# AD9434-500.net
KiCad netlist of a schematic drawn in Altium Designer
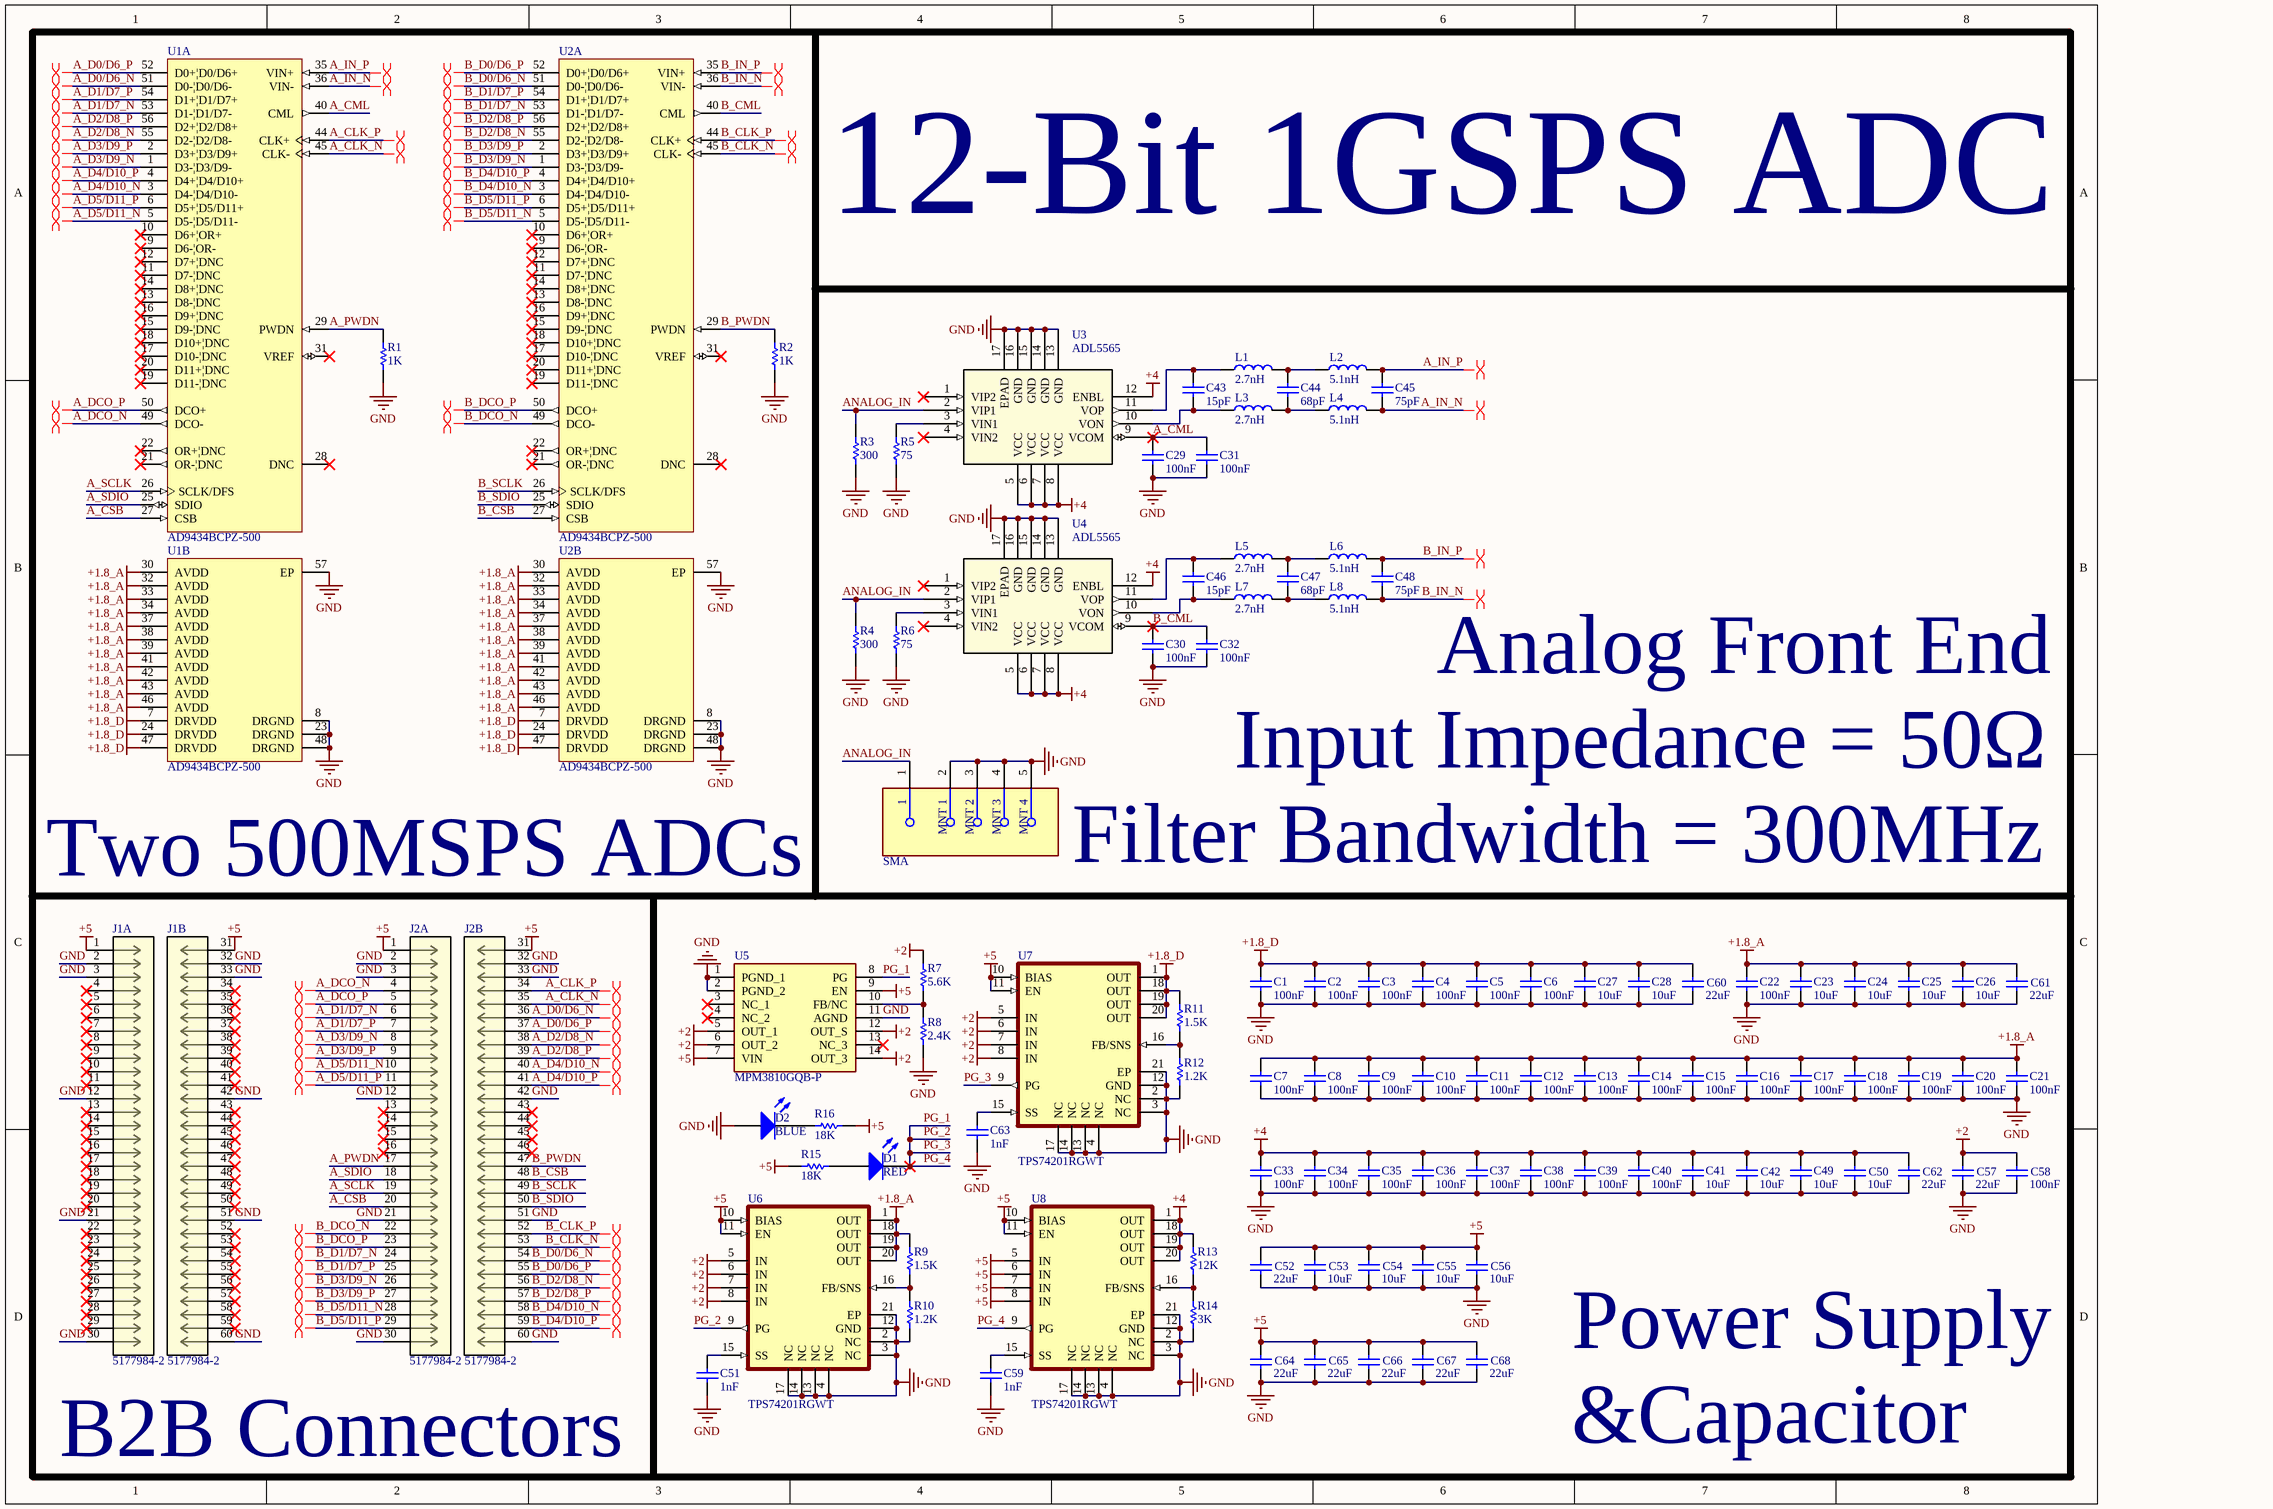
[diagram p0: AD9434-500.SchDoc]

(export (version "E")
  (design (tool "Eeschema 10.0.6"))
  (components
    (comp (ref "C1")
      (value "100nF")
      (footprint "0402")
      (description "Capacitor")
      (fields (field (name "PUBLISHER") "Altium Limited"))
      (libsource (lib "My Footprint") (part "CAP"))
    )
    (comp (ref "C2")
      (value "100nF")
      (footprint "0402")
      (description "Capacitor")
      (fields (field (name "PUBLISHER") "Altium Limited"))
      (libsource (lib "My Footprint") (part "CAP"))
    )
    (comp (ref "C3")
      (value "100nF")
      (footprint "0402")
      (description "Capacitor")
      (fields (field (name "PUBLISHER") "Altium Limited"))
      (libsource (lib "My Footprint") (part "CAP"))
    )
    (comp (ref "C4")
      (value "100nF")
      (footprint "0402")
      (description "Capacitor")
      (fields (field (name "PUBLISHER") "Altium Limited"))
      (libsource (lib "My Footprint") (part "CAP"))
    )
    (comp (ref "C5")
      (value "100nF")
      (footprint "0402")
      (description "Capacitor")
      (fields (field (name "PUBLISHER") "Altium Limited"))
      (libsource (lib "My Footprint") (part "CAP"))
    )
    (comp (ref "C6")
      (value "100nF")
      (footprint "0402")
      (description "Capacitor")
      (fields (field (name "PUBLISHER") "Altium Limited"))
      (libsource (lib "My Footprint") (part "CAP"))
    )
    (comp (ref "C7")
      (value "100nF")
      (footprint "0402")
      (description "Capacitor")
      (fields (field (name "PUBLISHER") "Altium Limited"))
      (libsource (lib "My Footprint") (part "CAP"))
    )
    (comp (ref "C8")
      (value "100nF")
      (footprint "0402")
      (description "Capacitor")
      (fields (field (name "PUBLISHER") "Altium Limited"))
      (libsource (lib "My Footprint") (part "CAP"))
    )
    (comp (ref "C9")
      (value "100nF")
      (footprint "0402")
      (description "Capacitor")
      (fields (field (name "PUBLISHER") "Altium Limited"))
      (libsource (lib "My Footprint") (part "CAP"))
    )
    (comp (ref "C10")
      (value "100nF")
      (footprint "0402")
      (description "Capacitor")
      (fields (field (name "PUBLISHER") "Altium Limited"))
      (libsource (lib "My Footprint") (part "CAP"))
    )
    (comp (ref "C11")
      (value "100nF")
      (footprint "0402")
      (description "Capacitor")
      (fields (field (name "PUBLISHER") "Altium Limited"))
      (libsource (lib "My Footprint") (part "CAP"))
    )
    (comp (ref "C12")
      (value "100nF")
      (footprint "0402")
      (description "Capacitor")
      (fields (field (name "PUBLISHER") "Altium Limited"))
      (libsource (lib "My Footprint") (part "CAP"))
    )
    (comp (ref "C13")
      (value "100nF")
      (footprint "0402")
      (description "Capacitor")
      (fields (field (name "PUBLISHER") "Altium Limited"))
      (libsource (lib "My Footprint") (part "CAP"))
    )
    (comp (ref "C14")
      (value "100nF")
      (footprint "0402")
      (description "Capacitor")
      (fields (field (name "PUBLISHER") "Altium Limited"))
      (libsource (lib "My Footprint") (part "CAP"))
    )
    (comp (ref "C15")
      (value "100nF")
      (footprint "0402")
      (description "Capacitor")
      (fields (field (name "PUBLISHER") "Altium Limited"))
      (libsource (lib "My Footprint") (part "CAP"))
    )
    (comp (ref "C16")
      (value "100nF")
      (footprint "0402")
      (description "Capacitor")
      (fields (field (name "PUBLISHER") "Altium Limited"))
      (libsource (lib "My Footprint") (part "CAP"))
    )
    (comp (ref "C17")
      (value "100nF")
      (footprint "0402")
      (description "Capacitor")
      (fields (field (name "PUBLISHER") "Altium Limited"))
      (libsource (lib "My Footprint") (part "CAP"))
    )
    (comp (ref "C18")
      (value "100nF")
      (footprint "0402")
      (description "Capacitor")
      (fields (field (name "PUBLISHER") "Altium Limited"))
      (libsource (lib "My Footprint") (part "CAP"))
    )
    (comp (ref "C19")
      (value "100nF")
      (footprint "0402")
      (description "Capacitor")
      (fields (field (name "PUBLISHER") "Altium Limited"))
      (libsource (lib "My Footprint") (part "CAP"))
    )
    (comp (ref "C20")
      (value "100nF")
      (footprint "0402")
      (description "Capacitor")
      (fields (field (name "PUBLISHER") "Altium Limited"))
      (libsource (lib "My Footprint") (part "CAP"))
    )
    (comp (ref "C21")
      (value "100nF")
      (footprint "0402")
      (description "Capacitor")
      (fields (field (name "PUBLISHER") "Altium Limited"))
      (libsource (lib "My Footprint") (part "CAP"))
    )
    (comp (ref "C22")
      (value "100nF")
      (footprint "0402")
      (description "Capacitor")
      (fields (field (name "PUBLISHER") "Altium Limited"))
      (libsource (lib "My Footprint") (part "CAP"))
    )
    (comp (ref "C23")
      (value "10uF")
      (footprint "0402")
      (description "Capacitor")
      (fields (field (name "PUBLISHER") "Altium Limited"))
      (libsource (lib "My Footprint") (part "CAP"))
    )
    (comp (ref "C24")
      (value "10uF")
      (footprint "0402")
      (description "Capacitor")
      (fields (field (name "PUBLISHER") "Altium Limited"))
      (libsource (lib "My Footprint") (part "CAP"))
    )
    (comp (ref "C25")
      (value "10uF")
      (footprint "0402")
      (description "Capacitor")
      (fields (field (name "PUBLISHER") "Altium Limited"))
      (libsource (lib "My Footprint") (part "CAP"))
    )
    (comp (ref "C26")
      (value "10uF")
      (footprint "0402")
      (description "Capacitor")
      (fields (field (name "PUBLISHER") "Altium Limited"))
      (libsource (lib "My Footprint") (part "CAP"))
    )
    (comp (ref "C27")
      (value "10uF")
      (footprint "0402")
      (description "Capacitor")
      (fields (field (name "PUBLISHER") "Altium Limited"))
      (libsource (lib "My Footprint") (part "CAP"))
    )
    (comp (ref "C28")
      (value "10uF")
      (footprint "0402")
      (description "Capacitor")
      (fields (field (name "PUBLISHER") "Altium Limited"))
      (libsource (lib "My Footprint") (part "CAP"))
    )
    (comp (ref "C29")
      (value "100nF")
      (footprint "0402")
      (description "Capacitor")
      (fields (field (name "PUBLISHER") "Altium Limited"))
      (libsource (lib "My Footprint") (part "CAP"))
    )
    (comp (ref "C30")
      (value "100nF")
      (footprint "0402")
      (description "Capacitor")
      (fields (field (name "PUBLISHER") "Altium Limited"))
      (libsource (lib "My Footprint") (part "CAP"))
    )
    (comp (ref "C31")
      (value "100nF")
      (footprint "0402")
      (description "Capacitor")
      (fields (field (name "PUBLISHER") "Altium Limited"))
      (libsource (lib "My Footprint") (part "CAP"))
    )
    (comp (ref "C32")
      (value "100nF")
      (footprint "0402")
      (description "Capacitor")
      (fields (field (name "PUBLISHER") "Altium Limited"))
      (libsource (lib "My Footprint") (part "CAP"))
    )
    (comp (ref "C33")
      (value "100nF")
      (footprint "0402")
      (description "Capacitor")
      (fields (field (name "PUBLISHER") "Altium Limited"))
      (libsource (lib "My Footprint") (part "CAP"))
    )
    (comp (ref "C34")
      (value "100nF")
      (footprint "0402")
      (description "Capacitor")
      (fields (field (name "PUBLISHER") "Altium Limited"))
      (libsource (lib "My Footprint") (part "CAP"))
    )
    (comp (ref "C35")
      (value "100nF")
      (footprint "0402")
      (description "Capacitor")
      (fields (field (name "PUBLISHER") "Altium Limited"))
      (libsource (lib "My Footprint") (part "CAP"))
    )
    (comp (ref "C36")
      (value "100nF")
      (footprint "0402")
      (description "Capacitor")
      (fields (field (name "PUBLISHER") "Altium Limited"))
      (libsource (lib "My Footprint") (part "CAP"))
    )
    (comp (ref "C37")
      (value "100nF")
      (footprint "0402")
      (description "Capacitor")
      (fields (field (name "PUBLISHER") "Altium Limited"))
      (libsource (lib "My Footprint") (part "CAP"))
    )
    (comp (ref "C38")
      (value "100nF")
      (footprint "0402")
      (description "Capacitor")
      (fields (field (name "PUBLISHER") "Altium Limited"))
      (libsource (lib "My Footprint") (part "CAP"))
    )
    (comp (ref "C39")
      (value "100nF")
      (footprint "0402")
      (description "Capacitor")
      (fields (field (name "PUBLISHER") "Altium Limited"))
      (libsource (lib "My Footprint") (part "CAP"))
    )
    (comp (ref "C40")
      (value "100nF")
      (footprint "0402")
      (description "Capacitor")
      (fields (field (name "PUBLISHER") "Altium Limited"))
      (libsource (lib "My Footprint") (part "CAP"))
    )
    (comp (ref "C41")
      (value "10uF")
      (footprint "0402")
      (description "Capacitor")
      (fields (field (name "PUBLISHER") "Altium Limited"))
      (libsource (lib "My Footprint") (part "CAP"))
    )
    (comp (ref "C42")
      (value "10uF")
      (footprint "0402")
      (description "Capacitor")
      (fields (field (name "PUBLISHER") "Altium Limited"))
      (libsource (lib "My Footprint") (part "CAP"))
    )
    (comp (ref "C43")
      (value "15pF")
      (footprint "0402")
      (description "Capacitor")
      (fields (field (name "PUBLISHER") "Altium Limited"))
      (libsource (lib "My Footprint") (part "CAP"))
    )
    (comp (ref "C44")
      (value "68pF")
      (footprint "0402")
      (description "Capacitor")
      (fields (field (name "PUBLISHER") "Altium Limited"))
      (libsource (lib "My Footprint") (part "CAP"))
    )
    (comp (ref "C45")
      (value "75pF")
      (footprint "0402")
      (description "Capacitor")
      (fields (field (name "PUBLISHER") "Altium Limited"))
      (libsource (lib "My Footprint") (part "CAP"))
    )
    (comp (ref "C46")
      (value "15pF")
      (footprint "0402")
      (description "Capacitor")
      (fields (field (name "PUBLISHER") "Altium Limited"))
      (libsource (lib "My Footprint") (part "CAP"))
    )
    (comp (ref "C47")
      (value "68pF")
      (footprint "0402")
      (description "Capacitor")
      (fields (field (name "PUBLISHER") "Altium Limited"))
      (libsource (lib "My Footprint") (part "CAP"))
    )
    (comp (ref "C48")
      (value "75pF")
      (footprint "0402")
      (description "Capacitor")
      (fields (field (name "PUBLISHER") "Altium Limited"))
      (libsource (lib "My Footprint") (part "CAP"))
    )
    (comp (ref "C49")
      (value "10uF")
      (footprint "0402")
      (description "Capacitor")
      (fields (field (name "PUBLISHER") "Altium Limited"))
      (libsource (lib "My Footprint") (part "CAP"))
    )
    (comp (ref "C50")
      (value "10uF")
      (footprint "0402")
      (description "Capacitor")
      (fields (field (name "PUBLISHER") "Altium Limited"))
      (libsource (lib "My Footprint") (part "CAP"))
    )
    (comp (ref "C51")
      (value "1nF")
      (footprint "0402")
      (description "Capacitor")
      (fields (field (name "PUBLISHER") "Altium Limited"))
      (libsource (lib "My Footprint") (part "CAP"))
    )
    (comp (ref "C52")
      (value "22uF")
      (footprint "6-0805_L")
      (description "Capacitor")
      (fields (field (name "PUBLISHER") "Altium Limited"))
      (libsource (lib "My Footprint") (part "CAP"))
    )
    (comp (ref "C53")
      (value "10uF")
      (footprint "0402")
      (description "Capacitor")
      (fields (field (name "PUBLISHER") "Altium Limited"))
      (libsource (lib "My Footprint") (part "CAP"))
    )
    (comp (ref "C54")
      (value "10uF")
      (footprint "0402")
      (description "Capacitor")
      (fields (field (name "PUBLISHER") "Altium Limited"))
      (libsource (lib "My Footprint") (part "CAP"))
    )
    (comp (ref "C55")
      (value "10uF")
      (footprint "0402")
      (description "Capacitor")
      (fields (field (name "PUBLISHER") "Altium Limited"))
      (libsource (lib "My Footprint") (part "CAP"))
    )
    (comp (ref "C56")
      (value "10uF")
      (footprint "0402")
      (description "Capacitor")
      (fields (field (name "PUBLISHER") "Altium Limited"))
      (libsource (lib "My Footprint") (part "CAP"))
    )
    (comp (ref "C57")
      (value "22uF")
      (footprint "6-0805_L")
      (description "Capacitor")
      (fields (field (name "PUBLISHER") "Altium Limited"))
      (libsource (lib "My Footprint") (part "CAP"))
    )
    (comp (ref "C58")
      (value "100nF")
      (footprint "0402")
      (description "Capacitor")
      (fields (field (name "PUBLISHER") "Altium Limited"))
      (libsource (lib "My Footprint") (part "CAP"))
    )
    (comp (ref "C59")
      (value "1nF")
      (footprint "0402")
      (description "Capacitor")
      (fields (field (name "PUBLISHER") "Altium Limited"))
      (libsource (lib "My Footprint") (part "CAP"))
    )
    (comp (ref "C60")
      (value "22uF")
      (footprint "6-0805_L")
      (description "Capacitor")
      (fields (field (name "PUBLISHER") "Altium Limited"))
      (libsource (lib "My Footprint") (part "CAP"))
    )
    (comp (ref "C61")
      (value "22uF")
      (footprint "6-0805_L")
      (description "Capacitor")
      (fields (field (name "PUBLISHER") "Altium Limited"))
      (libsource (lib "My Footprint") (part "CAP"))
    )
    (comp (ref "C62")
      (value "22uF")
      (footprint "6-0805_L")
      (description "Capacitor")
      (fields (field (name "PUBLISHER") "Altium Limited"))
      (libsource (lib "My Footprint") (part "CAP"))
    )
    (comp (ref "C63")
      (value "1nF")
      (footprint "0402")
      (description "Capacitor")
      (fields (field (name "PUBLISHER") "Altium Limited"))
      (libsource (lib "My Footprint") (part "CAP"))
    )
    (comp (ref "C64")
      (value "22uF")
      (footprint "6-0805_L")
      (description "Capacitor")
      (fields (field (name "PUBLISHER") "Altium Limited"))
      (libsource (lib "My Footprint") (part "CAP"))
    )
    (comp (ref "C65")
      (value "22uF")
      (footprint "6-0805_L")
      (description "Capacitor")
      (fields (field (name "PUBLISHER") "Altium Limited"))
      (libsource (lib "My Footprint") (part "CAP"))
    )
    (comp (ref "C66")
      (value "22uF")
      (footprint "6-0805_L")
      (description "Capacitor")
      (fields (field (name "PUBLISHER") "Altium Limited"))
      (libsource (lib "My Footprint") (part "CAP"))
    )
    (comp (ref "C67")
      (value "22uF")
      (footprint "6-0805_L")
      (description "Capacitor")
      (fields (field (name "PUBLISHER") "Altium Limited"))
      (libsource (lib "My Footprint") (part "CAP"))
    )
    (comp (ref "C68")
      (value "22uF")
      (footprint "6-0805_L")
      (description "Capacitor")
      (fields (field (name "PUBLISHER") "Altium Limited"))
      (libsource (lib "My Footprint") (part "CAP"))
    )
    (comp (ref "D1")
      (value "RED")
      (footprint "1608[0603]")
      (description "Typical INFRARED GaAs LED")
      (fields (field (name "PUBLISHER") "Altium Limited"))
      (libsource (lib "Miscellaneous Devices") (part "LED0"))
    )
    (comp (ref "D2")
      (value "BLUE")
      (footprint "1608[0603]")
      (description "Typical INFRARED GaAs LED")
      (fields (field (name "PUBLISHER") "Altium Limited"))
      (libsource (lib "Miscellaneous Devices") (part "LED0"))
    )
    (comp (ref "J1")
      (value "5177984-2")
      (footprint "CONN_5177984-2_TYC")
      (description "No Description Available")
      (fields (field (name "COPYRIGHT") "Copyright (C) 2022 Ultra Librarian. All rights reserved."))
      (libsource (lib "5177984-2") (part "5177984-2"))
    )
    (comp (ref "J2")
      (value "5177984-2")
      (footprint "CONN_5177984-2_TYC")
      (description "No Description Available")
      (fields (field (name "COPYRIGHT") "Copyright (C) 2022 Ultra Librarian. All rights reserved."))
      (libsource (lib "5177984-2") (part "5177984-2"))
    )
    (comp (ref "L1")
      (value "2.7nH")
      (footprint "0402")
      (description "磁珠")
      (libsource (lib "My Footprint") (part "FB"))
    )
    (comp (ref "L2")
      (value "5.1nH")
      (footprint "0402")
      (description "磁珠")
      (libsource (lib "My Footprint") (part "FB"))
    )
    (comp (ref "L3")
      (value "2.7nH")
      (footprint "0402")
      (description "磁珠")
      (libsource (lib "My Footprint") (part "FB"))
    )
    (comp (ref "L4")
      (value "5.1nH")
      (footprint "0402")
      (description "磁珠")
      (libsource (lib "My Footprint") (part "FB"))
    )
    (comp (ref "L5")
      (value "2.7nH")
      (footprint "0402")
      (description "磁珠")
      (libsource (lib "My Footprint") (part "FB"))
    )
    (comp (ref "L6")
      (value "5.1nH")
      (footprint "0402")
      (description "磁珠")
      (libsource (lib "My Footprint") (part "FB"))
    )
    (comp (ref "L7")
      (value "2.7nH")
      (footprint "0402")
      (description "磁珠")
      (libsource (lib "My Footprint") (part "FB"))
    )
    (comp (ref "L8")
      (value "5.1nH")
      (footprint "0402")
      (description "磁珠")
      (libsource (lib "My Footprint") (part "FB"))
    )
    (comp (ref "R1")
      (value "1K")
      (footprint "0402")
      (description "Resistor")
      (fields (field (name "PUBLISHER") "Altium Limited"))
      (libsource (lib "My Footprint") (part "RES"))
    )
    (comp (ref "R2")
      (value "1K")
      (footprint "0402")
      (description "Resistor")
      (fields (field (name "PUBLISHER") "Altium Limited"))
      (libsource (lib "My Footprint") (part "RES"))
    )
    (comp (ref "R3")
      (value "300")
      (footprint "0402")
      (description "Resistor")
      (fields (field (name "PUBLISHER") "Altium Limited"))
      (libsource (lib "My Footprint") (part "RES"))
    )
    (comp (ref "R4")
      (value "300")
      (footprint "0402")
      (description "Resistor")
      (fields (field (name "PUBLISHER") "Altium Limited"))
      (libsource (lib "My Footprint") (part "RES"))
    )
    (comp (ref "R5")
      (value "75")
      (footprint "0402")
      (description "Resistor")
      (fields (field (name "PUBLISHER") "Altium Limited"))
      (libsource (lib "My Footprint") (part "RES"))
    )
    (comp (ref "R6")
      (value "75")
      (footprint "0402")
      (description "Resistor")
      (fields (field (name "PUBLISHER") "Altium Limited"))
      (libsource (lib "My Footprint") (part "RES"))
    )
    (comp (ref "R7")
      (value "5.6K")
      (footprint "0402")
      (description "Resistor")
      (fields (field (name "PUBLISHER") "Altium Limited"))
      (libsource (lib "My Footprint") (part "RES"))
    )
    (comp (ref "R8")
      (value "2.4K")
      (footprint "0402")
      (description "Resistor")
      (fields (field (name "PUBLISHER") "Altium Limited"))
      (libsource (lib "My Footprint") (part "RES"))
    )
    (comp (ref "R9")
      (value "1.5K")
      (footprint "0402")
      (description "Resistor")
      (fields (field (name "PUBLISHER") "Altium Limited"))
      (libsource (lib "My Footprint") (part "RES"))
    )
    (comp (ref "R10")
      (value "1.2K")
      (footprint "0402")
      (description "Resistor")
      (fields (field (name "PUBLISHER") "Altium Limited"))
      (libsource (lib "My Footprint") (part "RES"))
    )
    (comp (ref "R11")
      (value "1.5K")
      (footprint "0402")
      (description "Resistor")
      (fields (field (name "PUBLISHER") "Altium Limited"))
      (libsource (lib "My Footprint") (part "RES"))
    )
    (comp (ref "R12")
      (value "1.2K")
      (footprint "0402")
      (description "Resistor")
      (fields (field (name "PUBLISHER") "Altium Limited"))
      (libsource (lib "My Footprint") (part "RES"))
    )
    (comp (ref "R13")
      (value "12K")
      (footprint "0402")
      (description "Resistor")
      (fields (field (name "PUBLISHER") "Altium Limited"))
      (libsource (lib "My Footprint") (part "RES"))
    )
    (comp (ref "R14")
      (value "3K")
      (footprint "0402")
      (description "Resistor")
      (fields (field (name "PUBLISHER") "Altium Limited"))
      (libsource (lib "My Footprint") (part "RES"))
    )
    (comp (ref "R15")
      (value "18K")
      (footprint "0402")
      (description "Resistor")
      (fields (field (name "PUBLISHER") "Altium Limited"))
      (libsource (lib "My Footprint") (part "RES"))
    )
    (comp (ref "R16")
      (value "18K")
      (footprint "0402")
      (description "Resistor")
      (fields (field (name "PUBLISHER") "Altium Limited"))
      (libsource (lib "My Footprint") (part "RES"))
    )
    (comp (ref "SMA")
      (value "1053354-1")
      (footprint "FP-1053354-1-MFG")
      (description "CONN SMA JACK STR 50 OHM PCB")
      (libsource (lib "Altium Content Vault") (part "c65b8a639cdaef1819ea20b5466f8fa"))
    )
    (comp (ref "U1")
      (value "AD9434BCPZ-500")
      (footprint "CP-56-5_L")
      (fields
        (field (name "GENERIC PART NUMBER") "AD9434-500")
        (field (name "MANUFACTURER") "Analog Devices")
      )
      (libsource (lib "AD9434-500") (part "CMP-0313-02358-2"))
    )
    (comp (ref "U2")
      (value "AD9434BCPZ-500")
      (footprint "CP-56-5_L")
      (fields
        (field (name "GENERIC PART NUMBER") "AD9434-500")
        (field (name "MANUFACTURER") "Analog Devices")
      )
      (libsource (lib "AD9434-500") (part "CMP-0313-02358-2"))
    )
    (comp (ref "U3")
      (value "ADL5565")
      (footprint "CP_16_2_ADI-L")
      (description "No Description Available")
      (fields (field (name "COPYRIGHT") "Copyright (C) 2022 Ultra Librarian. All rights reserved."))
      (libsource (lib "ADL5565") (part "ADL5565"))
    )
    (comp (ref "U4")
      (value "ADL5565")
      (footprint "CP_16_2_ADI-L")
      (description "No Description Available")
      (fields (field (name "COPYRIGHT") "Copyright (C) 2022 Ultra Librarian. All rights reserved."))
      (libsource (lib "ADL5565") (part "ADL5565"))
    )
    (comp (ref "U5")
      (value "MPM3810GQB-P")
      (footprint "SamacSys:MPM3810GQB33Z")
      (description "Integrated Circuit")
      (fields (field (name "MOUSER PART NUMBER") "946-MPM3810GQBP"))
      (libsource (lib "SamacSys") (part "MPM3810GQB-P"))
    )
    (comp (ref "U6")
      (value "TPS74201RGWT")
      (footprint "QFN65P500X500X100-21N")
      (libsource (lib "TPS74201") (part "TPS74201RGWT"))
    )
    (comp (ref "U7")
      (value "TPS74201RGWT")
      (footprint "QFN65P500X500X100-21N")
      (libsource (lib "TPS74201") (part "TPS74201RGWT"))
    )
    (comp (ref "U8")
      (value "TPS74201RGWT")
      (footprint "QFN65P500X500X100-21N")
      (libsource (lib "TPS74201") (part "TPS74201RGWT"))
    )
  )
  (nets
    (net (code "1") (name "+1.8_A") (class "Default")
      (node (ref "C10") (pin "1") (pinfunction "1_1") (pintype "passive"))
      (node (ref "C11") (pin "1") (pinfunction "1_1") (pintype "passive"))
      (node (ref "C12") (pin "1") (pinfunction "1_1") (pintype "passive"))
      (node (ref "C13") (pin "1") (pinfunction "1_1") (pintype "passive"))
      (node (ref "C14") (pin "1") (pinfunction "1_1") (pintype "passive"))
      (node (ref "C15") (pin "1") (pinfunction "1_1") (pintype "passive"))
      (node (ref "C16") (pin "1") (pinfunction "1_1") (pintype "passive"))
      (node (ref "C17") (pin "1") (pinfunction "1_1") (pintype "passive"))
      (node (ref "C18") (pin "1") (pinfunction "1_1") (pintype "passive"))
      (node (ref "C19") (pin "1") (pinfunction "1_1") (pintype "passive"))
      (node (ref "C20") (pin "1") (pinfunction "1_1") (pintype "passive"))
      (node (ref "C21") (pin "1") (pinfunction "1_1") (pintype "passive"))
      (node (ref "C22") (pin "1") (pinfunction "1_1") (pintype "passive"))
      (node (ref "C23") (pin "1") (pinfunction "1_1") (pintype "passive"))
      (node (ref "C24") (pin "1") (pinfunction "1_1") (pintype "passive"))
      (node (ref "C25") (pin "1") (pinfunction "1_1") (pintype "passive"))
      (node (ref "C26") (pin "1") (pinfunction "1_1") (pintype "passive"))
      (node (ref "C61") (pin "1") (pinfunction "1_1") (pintype "passive"))
      (node (ref "C7") (pin "1") (pinfunction "1_1") (pintype "passive"))
      (node (ref "C8") (pin "1") (pinfunction "1_1") (pintype "passive"))
      (node (ref "C9") (pin "1") (pinfunction "1_1") (pintype "passive"))
      (node (ref "R9") (pin "1") (pinfunction "1_1") (pintype "passive"))
      (node (ref "U1") (pin "30") (pinfunction "AVDD_30") (pintype "power_in"))
      (node (ref "U1") (pin "32") (pinfunction "AVDD_32") (pintype "power_in"))
      (node (ref "U1") (pin "33") (pinfunction "AVDD_33") (pintype "power_in"))
      (node (ref "U1") (pin "34") (pinfunction "AVDD_34") (pintype "power_in"))
      (node (ref "U1") (pin "37") (pinfunction "AVDD_37") (pintype "power_in"))
      (node (ref "U1") (pin "38") (pinfunction "AVDD_38") (pintype "power_in"))
      (node (ref "U1") (pin "39") (pinfunction "AVDD_39") (pintype "power_in"))
      (node (ref "U1") (pin "41") (pinfunction "AVDD_41") (pintype "power_in"))
      (node (ref "U1") (pin "42") (pinfunction "AVDD_42") (pintype "power_in"))
      (node (ref "U1") (pin "43") (pinfunction "AVDD_43") (pintype "power_in"))
      (node (ref "U1") (pin "46") (pinfunction "AVDD_46") (pintype "power_in"))
      (node (ref "U2") (pin "30") (pinfunction "AVDD_30") (pintype "power_in"))
      (node (ref "U2") (pin "32") (pinfunction "AVDD_32") (pintype "power_in"))
      (node (ref "U2") (pin "33") (pinfunction "AVDD_33") (pintype "power_in"))
      (node (ref "U2") (pin "34") (pinfunction "AVDD_34") (pintype "power_in"))
      (node (ref "U2") (pin "37") (pinfunction "AVDD_37") (pintype "power_in"))
      (node (ref "U2") (pin "38") (pinfunction "AVDD_38") (pintype "power_in"))
      (node (ref "U2") (pin "39") (pinfunction "AVDD_39") (pintype "power_in"))
      (node (ref "U2") (pin "41") (pinfunction "AVDD_41") (pintype "power_in"))
      (node (ref "U2") (pin "42") (pinfunction "AVDD_42") (pintype "power_in"))
      (node (ref "U2") (pin "43") (pinfunction "AVDD_43") (pintype "power_in"))
      (node (ref "U2") (pin "46") (pinfunction "AVDD_46") (pintype "power_in"))
      (node (ref "U6") (pin "1") (pinfunction "OUT_1") (pintype "passive"))
      (node (ref "U6") (pin "18") (pinfunction "OUT_18") (pintype "passive"))
      (node (ref "U6") (pin "19") (pinfunction "OUT_19") (pintype "passive"))
      (node (ref "U6") (pin "20") (pinfunction "OUT_20") (pintype "passive"))
    )
    (net (code "2") (name "+1.8_D") (class "Default")
      (node (ref "C1") (pin "1") (pinfunction "1_1") (pintype "passive"))
      (node (ref "C2") (pin "1") (pinfunction "1_1") (pintype "passive"))
      (node (ref "C27") (pin "1") (pinfunction "1_1") (pintype "passive"))
      (node (ref "C28") (pin "1") (pinfunction "1_1") (pintype "passive"))
      (node (ref "C3") (pin "1") (pinfunction "1_1") (pintype "passive"))
      (node (ref "C4") (pin "1") (pinfunction "1_1") (pintype "passive"))
      (node (ref "C5") (pin "1") (pinfunction "1_1") (pintype "passive"))
      (node (ref "C6") (pin "1") (pinfunction "1_1") (pintype "passive"))
      (node (ref "C60") (pin "1") (pinfunction "1_1") (pintype "passive"))
      (node (ref "R11") (pin "1") (pinfunction "1_1") (pintype "passive"))
      (node (ref "U1") (pin "24") (pinfunction "DRVDD_24") (pintype "power_in"))
      (node (ref "U1") (pin "47") (pinfunction "DRVDD_47") (pintype "power_in"))
      (node (ref "U1") (pin "7") (pinfunction "DRVDD_7") (pintype "power_in"))
      (node (ref "U2") (pin "24") (pinfunction "DRVDD_24") (pintype "power_in"))
      (node (ref "U2") (pin "47") (pinfunction "DRVDD_47") (pintype "power_in"))
      (node (ref "U2") (pin "7") (pinfunction "DRVDD_7") (pintype "power_in"))
      (node (ref "U7") (pin "1") (pinfunction "OUT_1") (pintype "passive"))
      (node (ref "U7") (pin "18") (pinfunction "OUT_18") (pintype "passive"))
      (node (ref "U7") (pin "19") (pinfunction "OUT_19") (pintype "passive"))
      (node (ref "U7") (pin "20") (pinfunction "OUT_20") (pintype "passive"))
    )
    (net (code "3") (name "+2") (class "Default")
      (node (ref "C57") (pin "1") (pinfunction "1_1") (pintype "passive"))
      (node (ref "C58") (pin "1") (pinfunction "1_1") (pintype "passive"))
      (node (ref "R7") (pin "1") (pinfunction "1_1") (pintype "passive"))
      (node (ref "U5") (pin "12") (pinfunction "OUT_S_12") (pintype "passive"))
      (node (ref "U5") (pin "14") (pinfunction "OUT_3_14") (pintype "passive"))
      (node (ref "U5") (pin "5") (pinfunction "OUT_1_5") (pintype "passive"))
      (node (ref "U5") (pin "6") (pinfunction "OUT_2_6") (pintype "passive"))
      (node (ref "U6") (pin "5") (pinfunction "IN_5") (pintype "passive"))
      (node (ref "U6") (pin "6") (pinfunction "IN_6") (pintype "passive"))
      (node (ref "U6") (pin "7") (pinfunction "IN_7") (pintype "passive"))
      (node (ref "U6") (pin "8") (pinfunction "IN_8") (pintype "passive"))
      (node (ref "U7") (pin "5") (pinfunction "IN_5") (pintype "passive"))
      (node (ref "U7") (pin "6") (pinfunction "IN_6") (pintype "passive"))
      (node (ref "U7") (pin "7") (pinfunction "IN_7") (pintype "passive"))
      (node (ref "U7") (pin "8") (pinfunction "IN_8") (pintype "passive"))
    )
    (net (code "4") (name "+4") (class "Default")
      (node (ref "C33") (pin "1") (pinfunction "1_1") (pintype "passive"))
      (node (ref "C34") (pin "1") (pinfunction "1_1") (pintype "passive"))
      (node (ref "C35") (pin "1") (pinfunction "1_1") (pintype "passive"))
      (node (ref "C36") (pin "1") (pinfunction "1_1") (pintype "passive"))
      (node (ref "C37") (pin "1") (pinfunction "1_1") (pintype "passive"))
      (node (ref "C38") (pin "1") (pinfunction "1_1") (pintype "passive"))
      (node (ref "C39") (pin "1") (pinfunction "1_1") (pintype "passive"))
      (node (ref "C40") (pin "1") (pinfunction "1_1") (pintype "passive"))
      (node (ref "C41") (pin "1") (pinfunction "1_1") (pintype "passive"))
      (node (ref "C42") (pin "1") (pinfunction "1_1") (pintype "passive"))
      (node (ref "C49") (pin "1") (pinfunction "1_1") (pintype "passive"))
      (node (ref "C50") (pin "1") (pinfunction "1_1") (pintype "passive"))
      (node (ref "C62") (pin "1") (pinfunction "1_1") (pintype "passive"))
      (node (ref "R13") (pin "1") (pinfunction "1_1") (pintype "passive"))
      (node (ref "U3") (pin "12") (pinfunction "ENBL_12") (pintype "passive"))
      (node (ref "U3") (pin "5") (pinfunction "VCC_5") (pintype "power_in"))
      (node (ref "U3") (pin "6") (pinfunction "VCC_6") (pintype "power_in"))
      (node (ref "U3") (pin "7") (pinfunction "VCC_7") (pintype "power_in"))
      (node (ref "U3") (pin "8") (pinfunction "VCC_8") (pintype "power_in"))
      (node (ref "U4") (pin "12") (pinfunction "ENBL_12") (pintype "passive"))
      (node (ref "U4") (pin "5") (pinfunction "VCC_5") (pintype "power_in"))
      (node (ref "U4") (pin "6") (pinfunction "VCC_6") (pintype "power_in"))
      (node (ref "U4") (pin "7") (pinfunction "VCC_7") (pintype "power_in"))
      (node (ref "U4") (pin "8") (pinfunction "VCC_8") (pintype "power_in"))
      (node (ref "U8") (pin "1") (pinfunction "OUT_1") (pintype "passive"))
      (node (ref "U8") (pin "18") (pinfunction "OUT_18") (pintype "passive"))
      (node (ref "U8") (pin "19") (pinfunction "OUT_19") (pintype "passive"))
      (node (ref "U8") (pin "20") (pinfunction "OUT_20") (pintype "passive"))
    )
    (net (code "5") (name "+5") (class "Default")
      (node (ref "C52") (pin "1") (pinfunction "1_1") (pintype "passive"))
      (node (ref "C53") (pin "1") (pinfunction "1_1") (pintype "passive"))
      (node (ref "C54") (pin "1") (pinfunction "1_1") (pintype "passive"))
      (node (ref "C55") (pin "1") (pinfunction "1_1") (pintype "passive"))
      (node (ref "C56") (pin "1") (pinfunction "1_1") (pintype "passive"))
      (node (ref "C64") (pin "1") (pinfunction "1_1") (pintype "passive"))
      (node (ref "C65") (pin "1") (pinfunction "1_1") (pintype "passive"))
      (node (ref "C66") (pin "1") (pinfunction "1_1") (pintype "passive"))
      (node (ref "C67") (pin "1") (pinfunction "1_1") (pintype "passive"))
      (node (ref "C68") (pin "1") (pinfunction "1_1") (pintype "passive"))
      (node (ref "J1") (pin "1") (pinfunction "1_1") (pintype "passive"))
      (node (ref "J1") (pin "31") (pinfunction "31_31") (pintype "passive"))
      (node (ref "J2") (pin "1") (pinfunction "1_1") (pintype "passive"))
      (node (ref "J2") (pin "31") (pinfunction "31_31") (pintype "passive"))
      (node (ref "R15") (pin "1") (pinfunction "1_1") (pintype "passive"))
      (node (ref "R16") (pin "2") (pinfunction "2_2") (pintype "passive"))
      (node (ref "U5") (pin "7") (pinfunction "VIN_7") (pintype "passive"))
      (node (ref "U5") (pin "9") (pinfunction "EN_9") (pintype "passive"))
      (node (ref "U6") (pin "10") (pinfunction "BIAS_10") (pintype "input"))
      (node (ref "U6") (pin "11") (pinfunction "EN_11") (pintype "input"))
      (node (ref "U7") (pin "10") (pinfunction "BIAS_10") (pintype "input"))
      (node (ref "U7") (pin "11") (pinfunction "EN_11") (pintype "input"))
      (node (ref "U8") (pin "10") (pinfunction "BIAS_10") (pintype "input"))
      (node (ref "U8") (pin "11") (pinfunction "EN_11") (pintype "input"))
      (node (ref "U8") (pin "5") (pinfunction "IN_5") (pintype "passive"))
      (node (ref "U8") (pin "6") (pinfunction "IN_6") (pintype "passive"))
      (node (ref "U8") (pin "7") (pinfunction "IN_7") (pintype "passive"))
      (node (ref "U8") (pin "8") (pinfunction "IN_8") (pintype "passive"))
    )
    (net (code "6") (name "/ANALOG_IN") (class "Default")
      (node (ref "R3") (pin "1") (pinfunction "1_1") (pintype "passive"))
      (node (ref "R4") (pin "1") (pinfunction "1_1") (pintype "passive"))
      (node (ref "SMA") (pin "1") (pinfunction "1_1") (pintype "passive"))
      (node (ref "U3") (pin "2") (pinfunction "VIP1_2") (pintype "input"))
      (node (ref "U4") (pin "2") (pinfunction "VIP1_2") (pintype "input"))
    )
    (net (code "7") (name "/A_CLK_N") (class "Default")
      (node (ref "J2") (pin "35") (pinfunction "35_35") (pintype "passive"))
      (node (ref "U1") (pin "45") (pinfunction "CLK-_45") (pintype "input"))
    )
    (net (code "8") (name "/A_CLK_P") (class "Default")
      (node (ref "J2") (pin "34") (pinfunction "34_34") (pintype "passive"))
      (node (ref "U1") (pin "44") (pinfunction "CLK+_44") (pintype "input"))
    )
    (net (code "9") (name "/A_CML") (class "Default")
      (node (ref "C29") (pin "1") (pinfunction "1_1") (pintype "passive"))
      (node (ref "C31") (pin "1") (pinfunction "1_1") (pintype "passive"))
      (node (ref "U1") (pin "40") (pinfunction "CML_40") (pintype "output"))
      (node (ref "U3") (pin "9") (pinfunction "VCOM_9") (pintype "bidirectional"))
    )
    (net (code "10") (name "/A_CSB") (class "Default")
      (node (ref "J2") (pin "20") (pinfunction "20_20") (pintype "passive"))
      (node (ref "U1") (pin "27") (pinfunction "CSB_27") (pintype "input"))
    )
    (net (code "11") (name "/A_D0{slash}D6_N") (class "Default")
      (node (ref "J2") (pin "36") (pinfunction "36_36") (pintype "passive"))
      (node (ref "U1") (pin "51") (pinfunction "D0-¦D0/D6-_51") (pintype "tri_state"))
    )
    (net (code "12") (name "/A_D0{slash}D6_P") (class "Default")
      (node (ref "J2") (pin "37") (pinfunction "37_37") (pintype "passive"))
      (node (ref "U1") (pin "52") (pinfunction "D0+¦D0/D6+_52") (pintype "tri_state"))
    )
    (net (code "13") (name "/A_D1{slash}D7_N") (class "Default")
      (node (ref "J2") (pin "6") (pinfunction "6_6") (pintype "passive"))
      (node (ref "U1") (pin "53") (pinfunction "D1-¦D1/D7-_53") (pintype "tri_state"))
    )
    (net (code "14") (name "/A_D1{slash}D7_P") (class "Default")
      (node (ref "J2") (pin "7") (pinfunction "7_7") (pintype "passive"))
      (node (ref "U1") (pin "54") (pinfunction "D1+¦D1/D7+_54") (pintype "tri_state"))
    )
    (net (code "15") (name "/A_D2{slash}D8_N") (class "Default")
      (node (ref "J2") (pin "38") (pinfunction "38_38") (pintype "passive"))
      (node (ref "U1") (pin "55") (pinfunction "D2-¦D2/D8-_55") (pintype "tri_state"))
    )
    (net (code "16") (name "/A_D2{slash}D8_P") (class "Default")
      (node (ref "J2") (pin "39") (pinfunction "39_39") (pintype "passive"))
      (node (ref "U1") (pin "56") (pinfunction "D2+¦D2/D8+_56") (pintype "tri_state"))
    )
    (net (code "17") (name "/A_D3{slash}D9_N") (class "Default")
      (node (ref "J2") (pin "8") (pinfunction "8_8") (pintype "passive"))
      (node (ref "U1") (pin "1") (pinfunction "D3-¦D3/D9-_1") (pintype "tri_state"))
    )
    (net (code "18") (name "/A_D3{slash}D9_P") (class "Default")
      (node (ref "J2") (pin "9") (pinfunction "9_9") (pintype "passive"))
      (node (ref "U1") (pin "2") (pinfunction "D3+¦D3/D9+_2") (pintype "tri_state"))
    )
    (net (code "19") (name "/A_D4{slash}D10_N") (class "Default")
      (node (ref "J2") (pin "40") (pinfunction "40_40") (pintype "passive"))
      (node (ref "U1") (pin "3") (pinfunction "D4-¦D4/D10-_3") (pintype "tri_state"))
    )
    (net (code "20") (name "/A_D4{slash}D10_P") (class "Default")
      (node (ref "J2") (pin "41") (pinfunction "41_41") (pintype "passive"))
      (node (ref "U1") (pin "4") (pinfunction "D4+¦D4/D10+_4") (pintype "tri_state"))
    )
    (net (code "21") (name "/A_D5{slash}D11_N") (class "Default")
      (node (ref "J2") (pin "10") (pinfunction "10_10") (pintype "passive"))
      (node (ref "U1") (pin "5") (pinfunction "D5-¦D5/D11-_5") (pintype "tri_state"))
    )
    (net (code "22") (name "/A_D5{slash}D11_P") (class "Default")
      (node (ref "J2") (pin "11") (pinfunction "11_11") (pintype "passive"))
      (node (ref "U1") (pin "6") (pinfunction "D5+¦D5/D11+_6") (pintype "tri_state"))
    )
    (net (code "23") (name "/A_DCO_N") (class "Default")
      (node (ref "J2") (pin "4") (pinfunction "4_4") (pintype "passive"))
      (node (ref "U1") (pin "49") (pinfunction "DCO-_49") (pintype "output"))
    )
    (net (code "24") (name "/A_DCO_P") (class "Default")
      (node (ref "J2") (pin "5") (pinfunction "5_5") (pintype "passive"))
      (node (ref "U1") (pin "50") (pinfunction "DCO+_50") (pintype "output"))
    )
    (net (code "25") (name "/A_IN_N") (class "Default")
      (node (ref "C45") (pin "2") (pinfunction "2_2") (pintype "passive"))
      (node (ref "L4") (pin "2") (pinfunction "2_2") (pintype "passive"))
      (node (ref "U1") (pin "36") (pinfunction "VIN-_36") (pintype "input"))
    )
    (net (code "26") (name "/A_IN_P") (class "Default")
      (node (ref "C45") (pin "1") (pinfunction "1_1") (pintype "passive"))
      (node (ref "L2") (pin "2") (pinfunction "2_2") (pintype "passive"))
      (node (ref "U1") (pin "35") (pinfunction "VIN+_35") (pintype "input"))
    )
    (net (code "27") (name "/A_PWDN") (class "Default")
      (node (ref "J2") (pin "17") (pinfunction "17_17") (pintype "passive"))
      (node (ref "R1") (pin "2") (pinfunction "2_2") (pintype "passive"))
      (node (ref "U1") (pin "29") (pinfunction "PWDN_29") (pintype "input"))
    )
    (net (code "28") (name "/A_SCLK") (class "Default")
      (node (ref "J2") (pin "19") (pinfunction "19_19") (pintype "passive"))
      (node (ref "U1") (pin "26") (pinfunction "SCLK/DFS_26") (pintype "input"))
    )
    (net (code "29") (name "/A_SDIO") (class "Default")
      (node (ref "J2") (pin "18") (pinfunction "18_18") (pintype "passive"))
      (node (ref "U1") (pin "25") (pinfunction "SDIO_25") (pintype "bidirectional"))
    )
    (net (code "30") (name "/B_CLK_N") (class "Default")
      (node (ref "J2") (pin "53") (pinfunction "53_53") (pintype "passive"))
      (node (ref "U2") (pin "45") (pinfunction "CLK-_45") (pintype "input"))
    )
    (net (code "31") (name "/B_CLK_P") (class "Default")
      (node (ref "J2") (pin "52") (pinfunction "52_52") (pintype "passive"))
      (node (ref "U2") (pin "44") (pinfunction "CLK+_44") (pintype "input"))
    )
    (net (code "32") (name "/B_CML") (class "Default")
      (node (ref "C30") (pin "1") (pinfunction "1_1") (pintype "passive"))
      (node (ref "C32") (pin "1") (pinfunction "1_1") (pintype "passive"))
      (node (ref "U2") (pin "40") (pinfunction "CML_40") (pintype "output"))
      (node (ref "U4") (pin "9") (pinfunction "VCOM_9") (pintype "bidirectional"))
    )
    (net (code "33") (name "/B_CSB") (class "Default")
      (node (ref "J2") (pin "48") (pinfunction "48_48") (pintype "passive"))
      (node (ref "U2") (pin "27") (pinfunction "CSB_27") (pintype "input"))
    )
    (net (code "34") (name "/B_D0{slash}D6_N") (class "Default")
      (node (ref "J2") (pin "54") (pinfunction "54_54") (pintype "passive"))
      (node (ref "U2") (pin "51") (pinfunction "D0-¦D0/D6-_51") (pintype "tri_state"))
    )
    (net (code "35") (name "/B_D0{slash}D6_P") (class "Default")
      (node (ref "J2") (pin "55") (pinfunction "55_55") (pintype "passive"))
      (node (ref "U2") (pin "52") (pinfunction "D0+¦D0/D6+_52") (pintype "tri_state"))
    )
    (net (code "36") (name "/B_D1{slash}D7_N") (class "Default")
      (node (ref "J2") (pin "24") (pinfunction "24_24") (pintype "passive"))
      (node (ref "U2") (pin "53") (pinfunction "D1-¦D1/D7-_53") (pintype "tri_state"))
    )
    (net (code "37") (name "/B_D1{slash}D7_P") (class "Default")
      (node (ref "J2") (pin "25") (pinfunction "25_25") (pintype "passive"))
      (node (ref "U2") (pin "54") (pinfunction "D1+¦D1/D7+_54") (pintype "tri_state"))
    )
    (net (code "38") (name "/B_D2{slash}D8_N") (class "Default")
      (node (ref "J2") (pin "56") (pinfunction "56_56") (pintype "passive"))
      (node (ref "U2") (pin "55") (pinfunction "D2-¦D2/D8-_55") (pintype "tri_state"))
    )
    (net (code "39") (name "/B_D2{slash}D8_P") (class "Default")
      (node (ref "J2") (pin "57") (pinfunction "57_57") (pintype "passive"))
      (node (ref "U2") (pin "56") (pinfunction "D2+¦D2/D8+_56") (pintype "tri_state"))
    )
    (net (code "40") (name "/B_D3{slash}D9_N") (class "Default")
      (node (ref "J2") (pin "26") (pinfunction "26_26") (pintype "passive"))
      (node (ref "U2") (pin "1") (pinfunction "D3-¦D3/D9-_1") (pintype "tri_state"))
    )
    (net (code "41") (name "/B_D3{slash}D9_P") (class "Default")
      (node (ref "J2") (pin "27") (pinfunction "27_27") (pintype "passive"))
      (node (ref "U2") (pin "2") (pinfunction "D3+¦D3/D9+_2") (pintype "tri_state"))
    )
    (net (code "42") (name "/B_D4{slash}D10_N") (class "Default")
      (node (ref "J2") (pin "58") (pinfunction "58_58") (pintype "passive"))
      (node (ref "U2") (pin "3") (pinfunction "D4-¦D4/D10-_3") (pintype "tri_state"))
    )
    (net (code "43") (name "/B_D4{slash}D10_P") (class "Default")
      (node (ref "J2") (pin "59") (pinfunction "59_59") (pintype "passive"))
      (node (ref "U2") (pin "4") (pinfunction "D4+¦D4/D10+_4") (pintype "tri_state"))
    )
    (net (code "44") (name "/B_D5{slash}D11_N") (class "Default")
      (node (ref "J2") (pin "28") (pinfunction "28_28") (pintype "passive"))
      (node (ref "U2") (pin "5") (pinfunction "D5-¦D5/D11-_5") (pintype "tri_state"))
    )
    (net (code "45") (name "/B_D5{slash}D11_P") (class "Default")
      (node (ref "J2") (pin "29") (pinfunction "29_29") (pintype "passive"))
      (node (ref "U2") (pin "6") (pinfunction "D5+¦D5/D11+_6") (pintype "tri_state"))
    )
    (net (code "46") (name "/B_DCO_N") (class "Default")
      (node (ref "J2") (pin "22") (pinfunction "22_22") (pintype "passive"))
      (node (ref "U2") (pin "49") (pinfunction "DCO-_49") (pintype "output"))
    )
    (net (code "47") (name "/B_DCO_P") (class "Default")
      (node (ref "J2") (pin "23") (pinfunction "23_23") (pintype "passive"))
      (node (ref "U2") (pin "50") (pinfunction "DCO+_50") (pintype "output"))
    )
    (net (code "48") (name "/B_IN_N") (class "Default")
      (node (ref "C48") (pin "2") (pinfunction "2_2") (pintype "passive"))
      (node (ref "L8") (pin "2") (pinfunction "2_2") (pintype "passive"))
      (node (ref "U2") (pin "36") (pinfunction "VIN-_36") (pintype "input"))
    )
    (net (code "49") (name "/B_IN_P") (class "Default")
      (node (ref "C48") (pin "1") (pinfunction "1_1") (pintype "passive"))
      (node (ref "L6") (pin "2") (pinfunction "2_2") (pintype "passive"))
      (node (ref "U2") (pin "35") (pinfunction "VIN+_35") (pintype "input"))
    )
    (net (code "50") (name "/B_PWDN") (class "Default")
      (node (ref "J2") (pin "47") (pinfunction "47_47") (pintype "passive"))
      (node (ref "R2") (pin "2") (pinfunction "2_2") (pintype "passive"))
      (node (ref "U2") (pin "29") (pinfunction "PWDN_29") (pintype "input"))
    )
    (net (code "51") (name "/B_SCLK") (class "Default")
      (node (ref "J2") (pin "49") (pinfunction "49_49") (pintype "passive"))
      (node (ref "U2") (pin "26") (pinfunction "SCLK/DFS_26") (pintype "input"))
    )
    (net (code "52") (name "/B_SDIO") (class "Default")
      (node (ref "J2") (pin "50") (pinfunction "50_50") (pintype "passive"))
      (node (ref "U2") (pin "25") (pinfunction "SDIO_25") (pintype "bidirectional"))
    )
    (net (code "53") (name "/PG_1") (class "Default")
      (node (ref "D1") (pin "2") (pinfunction "K_2") (pintype "passive"))
      (node (ref "U5") (pin "8") (pinfunction "PG_8") (pintype "passive"))
      (node (ref "U6") (pin "9") (pinfunction "PG_9") (pintype "output"))
      (node (ref "U7") (pin "9") (pinfunction "PG_9") (pintype "output"))
      (node (ref "U8") (pin "9") (pinfunction "PG_9") (pintype "output"))
    )
    (net (code "54") (name "GND") (class "Default")
      (node (ref "C1") (pin "2") (pinfunction "2_2") (pintype "passive"))
      (node (ref "C10") (pin "2") (pinfunction "2_2") (pintype "passive"))
      (node (ref "C11") (pin "2") (pinfunction "2_2") (pintype "passive"))
      (node (ref "C12") (pin "2") (pinfunction "2_2") (pintype "passive"))
      (node (ref "C13") (pin "2") (pinfunction "2_2") (pintype "passive"))
      (node (ref "C14") (pin "2") (pinfunction "2_2") (pintype "passive"))
      (node (ref "C15") (pin "2") (pinfunction "2_2") (pintype "passive"))
      (node (ref "C16") (pin "2") (pinfunction "2_2") (pintype "passive"))
      (node (ref "C17") (pin "2") (pinfunction "2_2") (pintype "passive"))
      (node (ref "C18") (pin "2") (pinfunction "2_2") (pintype "passive"))
      (node (ref "C19") (pin "2") (pinfunction "2_2") (pintype "passive"))
      (node (ref "C2") (pin "2") (pinfunction "2_2") (pintype "passive"))
      (node (ref "C20") (pin "2") (pinfunction "2_2") (pintype "passive"))
      (node (ref "C21") (pin "2") (pinfunction "2_2") (pintype "passive"))
      (node (ref "C22") (pin "2") (pinfunction "2_2") (pintype "passive"))
      (node (ref "C23") (pin "2") (pinfunction "2_2") (pintype "passive"))
      (node (ref "C24") (pin "2") (pinfunction "2_2") (pintype "passive"))
      (node (ref "C25") (pin "2") (pinfunction "2_2") (pintype "passive"))
      (node (ref "C26") (pin "2") (pinfunction "2_2") (pintype "passive"))
      (node (ref "C27") (pin "2") (pinfunction "2_2") (pintype "passive"))
      (node (ref "C28") (pin "2") (pinfunction "2_2") (pintype "passive"))
      (node (ref "C29") (pin "2") (pinfunction "2_2") (pintype "passive"))
      (node (ref "C3") (pin "2") (pinfunction "2_2") (pintype "passive"))
      (node (ref "C30") (pin "2") (pinfunction "2_2") (pintype "passive"))
      (node (ref "C31") (pin "2") (pinfunction "2_2") (pintype "passive"))
      (node (ref "C32") (pin "2") (pinfunction "2_2") (pintype "passive"))
      (node (ref "C33") (pin "2") (pinfunction "2_2") (pintype "passive"))
      (node (ref "C34") (pin "2") (pinfunction "2_2") (pintype "passive"))
      (node (ref "C35") (pin "2") (pinfunction "2_2") (pintype "passive"))
      (node (ref "C36") (pin "2") (pinfunction "2_2") (pintype "passive"))
      (node (ref "C37") (pin "2") (pinfunction "2_2") (pintype "passive"))
      (node (ref "C38") (pin "2") (pinfunction "2_2") (pintype "passive"))
      (node (ref "C39") (pin "2") (pinfunction "2_2") (pintype "passive"))
      (node (ref "C4") (pin "2") (pinfunction "2_2") (pintype "passive"))
      (node (ref "C40") (pin "2") (pinfunction "2_2") (pintype "passive"))
      (node (ref "C41") (pin "2") (pinfunction "2_2") (pintype "passive"))
      (node (ref "C42") (pin "2") (pinfunction "2_2") (pintype "passive"))
      (node (ref "C49") (pin "2") (pinfunction "2_2") (pintype "passive"))
      (node (ref "C5") (pin "2") (pinfunction "2_2") (pintype "passive"))
      (node (ref "C50") (pin "2") (pinfunction "2_2") (pintype "passive"))
      (node (ref "C51") (pin "2") (pinfunction "2_2") (pintype "passive"))
      (node (ref "C52") (pin "2") (pinfunction "2_2") (pintype "passive"))
      (node (ref "C53") (pin "2") (pinfunction "2_2") (pintype "passive"))
      (node (ref "C54") (pin "2") (pinfunction "2_2") (pintype "passive"))
      (node (ref "C55") (pin "2") (pinfunction "2_2") (pintype "passive"))
      (node (ref "C56") (pin "2") (pinfunction "2_2") (pintype "passive"))
      (node (ref "C57") (pin "2") (pinfunction "2_2") (pintype "passive"))
      (node (ref "C58") (pin "2") (pinfunction "2_2") (pintype "passive"))
      (node (ref "C59") (pin "2") (pinfunction "2_2") (pintype "passive"))
      (node (ref "C6") (pin "2") (pinfunction "2_2") (pintype "passive"))
      (node (ref "C60") (pin "2") (pinfunction "2_2") (pintype "passive"))
      (node (ref "C61") (pin "2") (pinfunction "2_2") (pintype "passive"))
      (node (ref "C62") (pin "2") (pinfunction "2_2") (pintype "passive"))
      (node (ref "C63") (pin "2") (pinfunction "2_2") (pintype "passive"))
      (node (ref "C64") (pin "2") (pinfunction "2_2") (pintype "passive"))
      (node (ref "C65") (pin "2") (pinfunction "2_2") (pintype "passive"))
      (node (ref "C66") (pin "2") (pinfunction "2_2") (pintype "passive"))
      (node (ref "C67") (pin "2") (pinfunction "2_2") (pintype "passive"))
      (node (ref "C68") (pin "2") (pinfunction "2_2") (pintype "passive"))
      (node (ref "C7") (pin "2") (pinfunction "2_2") (pintype "passive"))
      (node (ref "C8") (pin "2") (pinfunction "2_2") (pintype "passive"))
      (node (ref "C9") (pin "2") (pinfunction "2_2") (pintype "passive"))
      (node (ref "D2") (pin "1") (pinfunction "A_1") (pintype "passive"))
      (node (ref "J1") (pin "12") (pinfunction "12_12") (pintype "passive"))
      (node (ref "J1") (pin "2") (pinfunction "2_2") (pintype "passive"))
      (node (ref "J1") (pin "21") (pinfunction "21_21") (pintype "passive"))
      (node (ref "J1") (pin "3") (pinfunction "3_3") (pintype "passive"))
      (node (ref "J1") (pin "30") (pinfunction "30_30") (pintype "passive"))
      (node (ref "J1") (pin "32") (pinfunction "32_32") (pintype "passive"))
      (node (ref "J1") (pin "33") (pinfunction "33_33") (pintype "passive"))
      (node (ref "J1") (pin "42") (pinfunction "42_42") (pintype "passive"))
      (node (ref "J1") (pin "51") (pinfunction "51_51") (pintype "passive"))
      (node (ref "J1") (pin "60") (pinfunction "60_60") (pintype "passive"))
      (node (ref "J2") (pin "12") (pinfunction "12_12") (pintype "passive"))
      (node (ref "J2") (pin "2") (pinfunction "2_2") (pintype "passive"))
      (node (ref "J2") (pin "21") (pinfunction "21_21") (pintype "passive"))
      (node (ref "J2") (pin "3") (pinfunction "3_3") (pintype "passive"))
      (node (ref "J2") (pin "30") (pinfunction "30_30") (pintype "passive"))
      (node (ref "J2") (pin "32") (pinfunction "32_32") (pintype "passive"))
      (node (ref "J2") (pin "33") (pinfunction "33_33") (pintype "passive"))
      (node (ref "J2") (pin "42") (pinfunction "42_42") (pintype "passive"))
      (node (ref "J2") (pin "51") (pinfunction "51_51") (pintype "passive"))
      (node (ref "J2") (pin "60") (pinfunction "60_60") (pintype "passive"))
      (node (ref "R1") (pin "1") (pinfunction "1_1") (pintype "passive"))
      (node (ref "R10") (pin "2") (pinfunction "2_2") (pintype "passive"))
      (node (ref "R12") (pin "2") (pinfunction "2_2") (pintype "passive"))
      (node (ref "R14") (pin "2") (pinfunction "2_2") (pintype "passive"))
      (node (ref "R2") (pin "1") (pinfunction "1_1") (pintype "passive"))
      (node (ref "R3") (pin "2") (pinfunction "2_2") (pintype "passive"))
      (node (ref "R4") (pin "2") (pinfunction "2_2") (pintype "passive"))
      (node (ref "R5") (pin "2") (pinfunction "2_2") (pintype "passive"))
      (node (ref "R6") (pin "1") (pinfunction "1_1") (pintype "passive"))
      (node (ref "R8") (pin "2") (pinfunction "2_2") (pintype "passive"))
      (node (ref "SMA") (pin "2") (pinfunction "MNT_1_2") (pintype "passive"))
      (node (ref "SMA") (pin "3") (pinfunction "MNT_2_3") (pintype "passive"))
      (node (ref "SMA") (pin "4") (pinfunction "MNT_3_4") (pintype "passive"))
      (node (ref "SMA") (pin "5") (pinfunction "MNT_4_5") (pintype "passive"))
      (node (ref "U1") (pin "23") (pinfunction "DRGND_23") (pintype "power_in"))
      (node (ref "U1") (pin "48") (pinfunction "DRGND_48") (pintype "power_in"))
      (node (ref "U1") (pin "57") (pinfunction "EP_57") (pintype "power_in"))
      (node (ref "U1") (pin "8") (pinfunction "DRGND_8") (pintype "power_in"))
      (node (ref "U2") (pin "23") (pinfunction "DRGND_23") (pintype "power_in"))
      (node (ref "U2") (pin "48") (pinfunction "DRGND_48") (pintype "power_in"))
      (node (ref "U2") (pin "57") (pinfunction "EP_57") (pintype "power_in"))
      (node (ref "U2") (pin "8") (pinfunction "DRGND_8") (pintype "power_in"))
      (node (ref "U3") (pin "13") (pinfunction "GND_13") (pintype "power_in"))
      (node (ref "U3") (pin "14") (pinfunction "GND_14") (pintype "power_in"))
      (node (ref "U3") (pin "15") (pinfunction "GND_15") (pintype "power_in"))
      (node (ref "U3") (pin "16") (pinfunction "GND_16") (pintype "power_in"))
      (node (ref "U3") (pin "17") (pinfunction "EPAD_17") (pintype "passive"))
      (node (ref "U4") (pin "13") (pinfunction "GND_13") (pintype "power_in"))
      (node (ref "U4") (pin "14") (pinfunction "GND_14") (pintype "power_in"))
      (node (ref "U4") (pin "15") (pinfunction "GND_15") (pintype "power_in"))
      (node (ref "U4") (pin "16") (pinfunction "GND_16") (pintype "power_in"))
      (node (ref "U4") (pin "17") (pinfunction "EPAD_17") (pintype "passive"))
      (node (ref "U5") (pin "1") (pinfunction "PGND_1_1") (pintype "passive"))
      (node (ref "U5") (pin "11") (pinfunction "AGND_11") (pintype "passive"))
      (node (ref "U5") (pin "2") (pinfunction "PGND_2_2") (pintype "passive"))
      (node (ref "U6") (pin "12") (pinfunction "GND_12") (pintype "power_in"))
      (node (ref "U6") (pin "13") (pinfunction "NC_13") (pintype "power_in"))
      (node (ref "U6") (pin "14") (pinfunction "NC_14") (pintype "power_in"))
      (node (ref "U6") (pin "17") (pinfunction "NC_17") (pintype "power_in"))
      (node (ref "U6") (pin "2") (pinfunction "NC_2") (pintype "power_in"))
      (node (ref "U6") (pin "21") (pinfunction "EP_21") (pintype "passive"))
      (node (ref "U6") (pin "3") (pinfunction "NC_3") (pintype "power_in"))
      (node (ref "U6") (pin "4") (pinfunction "NC_4") (pintype "power_in"))
      (node (ref "U7") (pin "12") (pinfunction "GND_12") (pintype "power_in"))
      (node (ref "U7") (pin "13") (pinfunction "NC_13") (pintype "power_in"))
      (node (ref "U7") (pin "14") (pinfunction "NC_14") (pintype "power_in"))
      (node (ref "U7") (pin "17") (pinfunction "NC_17") (pintype "power_in"))
      (node (ref "U7") (pin "2") (pinfunction "NC_2") (pintype "power_in"))
      (node (ref "U7") (pin "21") (pinfunction "EP_21") (pintype "passive"))
      (node (ref "U7") (pin "3") (pinfunction "NC_3") (pintype "power_in"))
      (node (ref "U7") (pin "4") (pinfunction "NC_4") (pintype "power_in"))
      (node (ref "U8") (pin "12") (pinfunction "GND_12") (pintype "power_in"))
      (node (ref "U8") (pin "13") (pinfunction "NC_13") (pintype "power_in"))
      (node (ref "U8") (pin "14") (pinfunction "NC_14") (pintype "power_in"))
      (node (ref "U8") (pin "17") (pinfunction "NC_17") (pintype "power_in"))
      (node (ref "U8") (pin "2") (pinfunction "NC_2") (pintype "power_in"))
      (node (ref "U8") (pin "21") (pinfunction "EP_21") (pintype "passive"))
      (node (ref "U8") (pin "3") (pinfunction "NC_3") (pintype "power_in"))
      (node (ref "U8") (pin "4") (pinfunction "NC_4") (pintype "power_in"))
    )
    (net (code "55") (name "Net-(C44-Pad1)") (class "Default")
      (node (ref "C44") (pin "1") (pinfunction "1_1") (pintype "passive"))
      (node (ref "L1") (pin "2") (pinfunction "2_2") (pintype "passive"))
      (node (ref "L2") (pin "1") (pinfunction "1_1") (pintype "passive"))
    )
    (net (code "56") (name "Net-(C44-Pad2)") (class "Default")
      (node (ref "C44") (pin "2") (pinfunction "2_2") (pintype "passive"))
      (node (ref "L3") (pin "2") (pinfunction "2_2") (pintype "passive"))
      (node (ref "L4") (pin "1") (pinfunction "1_1") (pintype "passive"))
    )
    (net (code "57") (name "Net-(C47-Pad1)") (class "Default")
      (node (ref "C47") (pin "1") (pinfunction "1_1") (pintype "passive"))
      (node (ref "L5") (pin "2") (pinfunction "2_2") (pintype "passive"))
      (node (ref "L6") (pin "1") (pinfunction "1_1") (pintype "passive"))
    )
    (net (code "58") (name "Net-(C47-Pad2)") (class "Default")
      (node (ref "C47") (pin "2") (pinfunction "2_2") (pintype "passive"))
      (node (ref "L7") (pin "2") (pinfunction "2_2") (pintype "passive"))
      (node (ref "L8") (pin "1") (pinfunction "1_1") (pintype "passive"))
    )
    (net (code "59") (name "Net-(D1-A)") (class "Default")
      (node (ref "D1") (pin "1") (pinfunction "A_1") (pintype "passive"))
      (node (ref "R15") (pin "2") (pinfunction "2_2") (pintype "passive"))
    )
    (net (code "60") (name "Net-(D2-K)") (class "Default")
      (node (ref "D2") (pin "2") (pinfunction "K_2") (pintype "passive"))
      (node (ref "R16") (pin "1") (pinfunction "1_1") (pintype "passive"))
    )
    (net (code "61") (name "Net-(U3-VIN1)") (class "Default")
      (node (ref "R5") (pin "1") (pinfunction "1_1") (pintype "passive"))
      (node (ref "U3") (pin "3") (pinfunction "VIN1_3") (pintype "input"))
    )
    (net (code "62") (name "Net-(U3-VON)") (class "Default")
      (node (ref "C43") (pin "2") (pinfunction "2_2") (pintype "passive"))
      (node (ref "L3") (pin "1") (pinfunction "1_1") (pintype "passive"))
      (node (ref "U3") (pin "10") (pinfunction "VON_10") (pintype "output"))
    )
    (net (code "63") (name "Net-(U3-VOP)") (class "Default")
      (node (ref "C43") (pin "1") (pinfunction "1_1") (pintype "passive"))
      (node (ref "L1") (pin "1") (pinfunction "1_1") (pintype "passive"))
      (node (ref "U3") (pin "11") (pinfunction "VOP_11") (pintype "output"))
    )
    (net (code "64") (name "Net-(U4-VIN1)") (class "Default")
      (node (ref "R6") (pin "2") (pinfunction "2_2") (pintype "passive"))
      (node (ref "U4") (pin "3") (pinfunction "VIN1_3") (pintype "input"))
    )
    (net (code "65") (name "Net-(U4-VON)") (class "Default")
      (node (ref "C46") (pin "2") (pinfunction "2_2") (pintype "passive"))
      (node (ref "L7") (pin "1") (pinfunction "1_1") (pintype "passive"))
      (node (ref "U4") (pin "10") (pinfunction "VON_10") (pintype "output"))
    )
    (net (code "66") (name "Net-(U4-VOP)") (class "Default")
      (node (ref "C46") (pin "1") (pinfunction "1_1") (pintype "passive"))
      (node (ref "L5") (pin "1") (pinfunction "1_1") (pintype "passive"))
      (node (ref "U4") (pin "11") (pinfunction "VOP_11") (pintype "output"))
    )
    (net (code "67") (name "Net-(U5-FB{slash}NC)") (class "Default")
      (node (ref "R7") (pin "2") (pinfunction "2_2") (pintype "passive"))
      (node (ref "R8") (pin "1") (pinfunction "1_1") (pintype "passive"))
      (node (ref "U5") (pin "10") (pinfunction "FB/NC_10") (pintype "passive"))
    )
    (net (code "68") (name "Net-(U6-FB{slash}SNS)") (class "Default")
      (node (ref "R10") (pin "1") (pinfunction "1_1") (pintype "passive"))
      (node (ref "R9") (pin "2") (pinfunction "2_2") (pintype "passive"))
      (node (ref "U6") (pin "16") (pinfunction "FB/SNS_16") (pintype "input"))
    )
    (net (code "69") (name "Net-(U6-SS)") (class "Default")
      (node (ref "C51") (pin "1") (pinfunction "1_1") (pintype "passive"))
      (node (ref "U6") (pin "15") (pinfunction "SS_15") (pintype "input"))
    )
    (net (code "70") (name "Net-(U7-FB{slash}SNS)") (class "Default")
      (node (ref "R11") (pin "2") (pinfunction "2_2") (pintype "passive"))
      (node (ref "R12") (pin "1") (pinfunction "1_1") (pintype "passive"))
      (node (ref "U7") (pin "16") (pinfunction "FB/SNS_16") (pintype "input"))
    )
    (net (code "71") (name "Net-(U7-SS)") (class "Default")
      (node (ref "C63") (pin "1") (pinfunction "1_1") (pintype "passive"))
      (node (ref "U7") (pin "15") (pinfunction "SS_15") (pintype "input"))
    )
    (net (code "72") (name "Net-(U8-FB{slash}SNS)") (class "Default")
      (node (ref "R13") (pin "2") (pinfunction "2_2") (pintype "passive"))
      (node (ref "R14") (pin "1") (pinfunction "1_1") (pintype "passive"))
      (node (ref "U8") (pin "16") (pinfunction "FB/SNS_16") (pintype "input"))
    )
    (net (code "73") (name "Net-(U8-SS)") (class "Default")
      (node (ref "C59") (pin "1") (pinfunction "1_1") (pintype "passive"))
      (node (ref "U8") (pin "15") (pinfunction "SS_15") (pintype "input"))
    )
    (net (code "74") (name "unconnected-(J1-Pad4)") (class "Default")
      (node (ref "J1") (pin "4") (pinfunction "4_4") (pintype "passive+no_connect"))
    )
    (net (code "75") (name "unconnected-(J1-Pad5)") (class "Default")
      (node (ref "J1") (pin "5") (pinfunction "5_5") (pintype "passive+no_connect"))
    )
    (net (code "76") (name "unconnected-(J1-Pad6)") (class "Default")
      (node (ref "J1") (pin "6") (pinfunction "6_6") (pintype "passive+no_connect"))
    )
    (net (code "77") (name "unconnected-(J1-Pad7)") (class "Default")
      (node (ref "J1") (pin "7") (pinfunction "7_7") (pintype "passive+no_connect"))
    )
    (net (code "78") (name "unconnected-(J1-Pad8)") (class "Default")
      (node (ref "J1") (pin "8") (pinfunction "8_8") (pintype "passive+no_connect"))
    )
    (net (code "79") (name "unconnected-(J1-Pad9)") (class "Default")
      (node (ref "J1") (pin "9") (pinfunction "9_9") (pintype "passive+no_connect"))
    )
    (net (code "80") (name "unconnected-(J1-Pad10)") (class "Default")
      (node (ref "J1") (pin "10") (pinfunction "10_10") (pintype "passive+no_connect"))
    )
    (net (code "81") (name "unconnected-(J1-Pad11)") (class "Default")
      (node (ref "J1") (pin "11") (pinfunction "11_11") (pintype "passive+no_connect"))
    )
    (net (code "82") (name "unconnected-(J1-Pad13)") (class "Default")
      (node (ref "J1") (pin "13") (pinfunction "13_13") (pintype "passive+no_connect"))
    )
    (net (code "83") (name "unconnected-(J1-Pad14)") (class "Default")
      (node (ref "J1") (pin "14") (pinfunction "14_14") (pintype "passive+no_connect"))
    )
    (net (code "84") (name "unconnected-(J1-Pad15)") (class "Default")
      (node (ref "J1") (pin "15") (pinfunction "15_15") (pintype "passive+no_connect"))
    )
    (net (code "85") (name "unconnected-(J1-Pad16)") (class "Default")
      (node (ref "J1") (pin "16") (pinfunction "16_16") (pintype "passive+no_connect"))
    )
    (net (code "86") (name "unconnected-(J1-Pad17)") (class "Default")
      (node (ref "J1") (pin "17") (pinfunction "17_17") (pintype "passive+no_connect"))
    )
    (net (code "87") (name "unconnected-(J1-Pad18)") (class "Default")
      (node (ref "J1") (pin "18") (pinfunction "18_18") (pintype "passive+no_connect"))
    )
    (net (code "88") (name "unconnected-(J1-Pad19)") (class "Default")
      (node (ref "J1") (pin "19") (pinfunction "19_19") (pintype "passive+no_connect"))
    )
    (net (code "89") (name "unconnected-(J1-Pad20)") (class "Default")
      (node (ref "J1") (pin "20") (pinfunction "20_20") (pintype "passive+no_connect"))
    )
    (net (code "90") (name "unconnected-(J1-Pad22)") (class "Default")
      (node (ref "J1") (pin "22") (pinfunction "22_22") (pintype "passive+no_connect"))
    )
    (net (code "91") (name "unconnected-(J1-Pad23)") (class "Default")
      (node (ref "J1") (pin "23") (pinfunction "23_23") (pintype "passive+no_connect"))
    )
    (net (code "92") (name "unconnected-(J1-Pad24)") (class "Default")
      (node (ref "J1") (pin "24") (pinfunction "24_24") (pintype "passive+no_connect"))
    )
    (net (code "93") (name "unconnected-(J1-Pad25)") (class "Default")
      (node (ref "J1") (pin "25") (pinfunction "25_25") (pintype "passive+no_connect"))
    )
    (net (code "94") (name "unconnected-(J1-Pad26)") (class "Default")
      (node (ref "J1") (pin "26") (pinfunction "26_26") (pintype "passive+no_connect"))
    )
    (net (code "95") (name "unconnected-(J1-Pad27)") (class "Default")
      (node (ref "J1") (pin "27") (pinfunction "27_27") (pintype "passive+no_connect"))
    )
    (net (code "96") (name "unconnected-(J1-Pad28)") (class "Default")
      (node (ref "J1") (pin "28") (pinfunction "28_28") (pintype "passive+no_connect"))
    )
    (net (code "97") (name "unconnected-(J1-Pad29)") (class "Default")
      (node (ref "J1") (pin "29") (pinfunction "29_29") (pintype "passive+no_connect"))
    )
    (net (code "98") (name "unconnected-(J1-Pad34)") (class "Default")
      (node (ref "J1") (pin "34") (pinfunction "34_34") (pintype "passive+no_connect"))
    )
    (net (code "99") (name "unconnected-(J1-Pad35)") (class "Default")
      (node (ref "J1") (pin "35") (pinfunction "35_35") (pintype "passive+no_connect"))
    )
    (net (code "100") (name "unconnected-(J1-Pad36)") (class "Default")
      (node (ref "J1") (pin "36") (pinfunction "36_36") (pintype "passive+no_connect"))
    )
    (net (code "101") (name "unconnected-(J1-Pad37)") (class "Default")
      (node (ref "J1") (pin "37") (pinfunction "37_37") (pintype "passive+no_connect"))
    )
    (net (code "102") (name "unconnected-(J1-Pad38)") (class "Default")
      (node (ref "J1") (pin "38") (pinfunction "38_38") (pintype "passive+no_connect"))
    )
    (net (code "103") (name "unconnected-(J1-Pad39)") (class "Default")
      (node (ref "J1") (pin "39") (pinfunction "39_39") (pintype "passive+no_connect"))
    )
    (net (code "104") (name "unconnected-(J1-Pad40)") (class "Default")
      (node (ref "J1") (pin "40") (pinfunction "40_40") (pintype "passive+no_connect"))
    )
    (net (code "105") (name "unconnected-(J1-Pad41)") (class "Default")
      (node (ref "J1") (pin "41") (pinfunction "41_41") (pintype "passive+no_connect"))
    )
    (net (code "106") (name "unconnected-(J1-Pad43)") (class "Default")
      (node (ref "J1") (pin "43") (pinfunction "43_43") (pintype "passive+no_connect"))
    )
    (net (code "107") (name "unconnected-(J1-Pad44)") (class "Default")
      (node (ref "J1") (pin "44") (pinfunction "44_44") (pintype "passive+no_connect"))
    )
    (net (code "108") (name "unconnected-(J1-Pad45)") (class "Default")
      (node (ref "J1") (pin "45") (pinfunction "45_45") (pintype "passive+no_connect"))
    )
    (net (code "109") (name "unconnected-(J1-Pad46)") (class "Default")
      (node (ref "J1") (pin "46") (pinfunction "46_46") (pintype "passive+no_connect"))
    )
    (net (code "110") (name "unconnected-(J1-Pad47)") (class "Default")
      (node (ref "J1") (pin "47") (pinfunction "47_47") (pintype "passive+no_connect"))
    )
    (net (code "111") (name "unconnected-(J1-Pad48)") (class "Default")
      (node (ref "J1") (pin "48") (pinfunction "48_48") (pintype "passive+no_connect"))
    )
    (net (code "112") (name "unconnected-(J1-Pad49)") (class "Default")
      (node (ref "J1") (pin "49") (pinfunction "49_49") (pintype "passive+no_connect"))
    )
    (net (code "113") (name "unconnected-(J1-Pad50)") (class "Default")
      (node (ref "J1") (pin "50") (pinfunction "50_50") (pintype "passive+no_connect"))
    )
    (net (code "114") (name "unconnected-(J1-Pad52)") (class "Default")
      (node (ref "J1") (pin "52") (pinfunction "52_52") (pintype "passive+no_connect"))
    )
    (net (code "115") (name "unconnected-(J1-Pad53)") (class "Default")
      (node (ref "J1") (pin "53") (pinfunction "53_53") (pintype "passive+no_connect"))
    )
    (net (code "116") (name "unconnected-(J1-Pad54)") (class "Default")
      (node (ref "J1") (pin "54") (pinfunction "54_54") (pintype "passive+no_connect"))
    )
    (net (code "117") (name "unconnected-(J1-Pad55)") (class "Default")
      (node (ref "J1") (pin "55") (pinfunction "55_55") (pintype "passive+no_connect"))
    )
    (net (code "118") (name "unconnected-(J1-Pad56)") (class "Default")
      (node (ref "J1") (pin "56") (pinfunction "56_56") (pintype "passive+no_connect"))
    )
    (net (code "119") (name "unconnected-(J1-Pad57)") (class "Default")
      (node (ref "J1") (pin "57") (pinfunction "57_57") (pintype "passive+no_connect"))
    )
    (net (code "120") (name "unconnected-(J1-Pad58)") (class "Default")
      (node (ref "J1") (pin "58") (pinfunction "58_58") (pintype "passive+no_connect"))
    )
    (net (code "121") (name "unconnected-(J1-Pad59)") (class "Default")
      (node (ref "J1") (pin "59") (pinfunction "59_59") (pintype "passive+no_connect"))
    )
    (net (code "122") (name "unconnected-(J2-Pad13)") (class "Default")
      (node (ref "J2") (pin "13") (pinfunction "13_13") (pintype "passive+no_connect"))
    )
    (net (code "123") (name "unconnected-(J2-Pad14)") (class "Default")
      (node (ref "J2") (pin "14") (pinfunction "14_14") (pintype "passive+no_connect"))
    )
    (net (code "124") (name "unconnected-(J2-Pad15)") (class "Default")
      (node (ref "J2") (pin "15") (pinfunction "15_15") (pintype "passive+no_connect"))
    )
    (net (code "125") (name "unconnected-(J2-Pad16)") (class "Default")
      (node (ref "J2") (pin "16") (pinfunction "16_16") (pintype "passive+no_connect"))
    )
    (net (code "126") (name "unconnected-(J2-Pad43)") (class "Default")
      (node (ref "J2") (pin "43") (pinfunction "43_43") (pintype "passive+no_connect"))
    )
    (net (code "127") (name "unconnected-(J2-Pad44)") (class "Default")
      (node (ref "J2") (pin "44") (pinfunction "44_44") (pintype "passive+no_connect"))
    )
    (net (code "128") (name "unconnected-(J2-Pad45)") (class "Default")
      (node (ref "J2") (pin "45") (pinfunction "45_45") (pintype "passive+no_connect"))
    )
    (net (code "129") (name "unconnected-(J2-Pad46)") (class "Default")
      (node (ref "J2") (pin "46") (pinfunction "46_46") (pintype "passive+no_connect"))
    )
    (net (code "130") (name "unconnected-(U1A-D6+¦OR+-Pad10)") (class "Default")
      (node (ref "U1") (pin "10") (pinfunction "D6+¦OR+_10") (pintype "tri_state+no_connect"))
    )
    (net (code "131") (name "unconnected-(U1A-D6-¦OR--Pad9)") (class "Default")
      (node (ref "U1") (pin "9") (pinfunction "D6-¦OR-_9") (pintype "tri_state+no_connect"))
    )
    (net (code "132") (name "unconnected-(U1A-D7+¦DNC-Pad12)") (class "Default")
      (node (ref "U1") (pin "12") (pinfunction "D7+¦DNC_12") (pintype "tri_state+no_connect"))
    )
    (net (code "133") (name "unconnected-(U1A-D7-¦DNC-Pad11)") (class "Default")
      (node (ref "U1") (pin "11") (pinfunction "D7-¦DNC_11") (pintype "tri_state+no_connect"))
    )
    (net (code "134") (name "unconnected-(U1A-D8+¦DNC-Pad14)") (class "Default")
      (node (ref "U1") (pin "14") (pinfunction "D8+¦DNC_14") (pintype "tri_state+no_connect"))
    )
    (net (code "135") (name "unconnected-(U1A-D8-¦DNC-Pad13)") (class "Default")
      (node (ref "U1") (pin "13") (pinfunction "D8-¦DNC_13") (pintype "tri_state+no_connect"))
    )
    (net (code "136") (name "unconnected-(U1A-D9+¦DNC-Pad16)") (class "Default")
      (node (ref "U1") (pin "16") (pinfunction "D9+¦DNC_16") (pintype "tri_state+no_connect"))
    )
    (net (code "137") (name "unconnected-(U1A-D9-¦DNC-Pad15)") (class "Default")
      (node (ref "U1") (pin "15") (pinfunction "D9-¦DNC_15") (pintype "tri_state+no_connect"))
    )
    (net (code "138") (name "unconnected-(U1A-D10+¦DNC-Pad18)") (class "Default")
      (node (ref "U1") (pin "18") (pinfunction "D10+¦DNC_18") (pintype "tri_state+no_connect"))
    )
    (net (code "139") (name "unconnected-(U1A-D10-¦DNC-Pad17)") (class "Default")
      (node (ref "U1") (pin "17") (pinfunction "D10-¦DNC_17") (pintype "tri_state+no_connect"))
    )
    (net (code "140") (name "unconnected-(U1A-D11+¦DNC-Pad20)") (class "Default")
      (node (ref "U1") (pin "20") (pinfunction "D11+¦DNC_20") (pintype "tri_state+no_connect"))
    )
    (net (code "141") (name "unconnected-(U1A-D11-¦DNC-Pad19)") (class "Default")
      (node (ref "U1") (pin "19") (pinfunction "D11-¦DNC_19") (pintype "tri_state+no_connect"))
    )
    (net (code "142") (name "unconnected-(U1A-DNC-Pad28)") (class "Default")
      (node (ref "U1") (pin "28") (pinfunction "DNC_28") (pintype "passive+no_connect"))
    )
    (net (code "143") (name "unconnected-(U1A-OR+¦DNC-Pad22)") (class "Default")
      (node (ref "U1") (pin "22") (pinfunction "OR+¦DNC_22") (pintype "output+no_connect"))
    )
    (net (code "144") (name "unconnected-(U1A-OR-¦DNC-Pad21)") (class "Default")
      (node (ref "U1") (pin "21") (pinfunction "OR-¦DNC_21") (pintype "output+no_connect"))
    )
    (net (code "145") (name "unconnected-(U1A-VREF-Pad31)") (class "Default")
      (node (ref "U1") (pin "31") (pinfunction "VREF_31") (pintype "bidirectional+no_connect"))
    )
    (net (code "146") (name "unconnected-(U2A-D6+¦OR+-Pad10)") (class "Default")
      (node (ref "U2") (pin "10") (pinfunction "D6+¦OR+_10") (pintype "tri_state+no_connect"))
    )
    (net (code "147") (name "unconnected-(U2A-D6-¦OR--Pad9)") (class "Default")
      (node (ref "U2") (pin "9") (pinfunction "D6-¦OR-_9") (pintype "tri_state+no_connect"))
    )
    (net (code "148") (name "unconnected-(U2A-D7+¦DNC-Pad12)") (class "Default")
      (node (ref "U2") (pin "12") (pinfunction "D7+¦DNC_12") (pintype "tri_state+no_connect"))
    )
    (net (code "149") (name "unconnected-(U2A-D7-¦DNC-Pad11)") (class "Default")
      (node (ref "U2") (pin "11") (pinfunction "D7-¦DNC_11") (pintype "tri_state+no_connect"))
    )
    (net (code "150") (name "unconnected-(U2A-D8+¦DNC-Pad14)") (class "Default")
      (node (ref "U2") (pin "14") (pinfunction "D8+¦DNC_14") (pintype "tri_state+no_connect"))
    )
    (net (code "151") (name "unconnected-(U2A-D8-¦DNC-Pad13)") (class "Default")
      (node (ref "U2") (pin "13") (pinfunction "D8-¦DNC_13") (pintype "tri_state+no_connect"))
    )
    (net (code "152") (name "unconnected-(U2A-D9+¦DNC-Pad16)") (class "Default")
      (node (ref "U2") (pin "16") (pinfunction "D9+¦DNC_16") (pintype "tri_state+no_connect"))
    )
    (net (code "153") (name "unconnected-(U2A-D9-¦DNC-Pad15)") (class "Default")
      (node (ref "U2") (pin "15") (pinfunction "D9-¦DNC_15") (pintype "tri_state+no_connect"))
    )
    (net (code "154") (name "unconnected-(U2A-D10+¦DNC-Pad18)") (class "Default")
      (node (ref "U2") (pin "18") (pinfunction "D10+¦DNC_18") (pintype "tri_state+no_connect"))
    )
    (net (code "155") (name "unconnected-(U2A-D10-¦DNC-Pad17)") (class "Default")
      (node (ref "U2") (pin "17") (pinfunction "D10-¦DNC_17") (pintype "tri_state+no_connect"))
    )
    (net (code "156") (name "unconnected-(U2A-D11+¦DNC-Pad20)") (class "Default")
      (node (ref "U2") (pin "20") (pinfunction "D11+¦DNC_20") (pintype "tri_state+no_connect"))
    )
    (net (code "157") (name "unconnected-(U2A-D11-¦DNC-Pad19)") (class "Default")
      (node (ref "U2") (pin "19") (pinfunction "D11-¦DNC_19") (pintype "tri_state+no_connect"))
    )
    (net (code "158") (name "unconnected-(U2A-DNC-Pad28)") (class "Default")
      (node (ref "U2") (pin "28") (pinfunction "DNC_28") (pintype "passive+no_connect"))
    )
    (net (code "159") (name "unconnected-(U2A-OR+¦DNC-Pad22)") (class "Default")
      (node (ref "U2") (pin "22") (pinfunction "OR+¦DNC_22") (pintype "output+no_connect"))
    )
    (net (code "160") (name "unconnected-(U2A-OR-¦DNC-Pad21)") (class "Default")
      (node (ref "U2") (pin "21") (pinfunction "OR-¦DNC_21") (pintype "output+no_connect"))
    )
    (net (code "161") (name "unconnected-(U2A-VREF-Pad31)") (class "Default")
      (node (ref "U2") (pin "31") (pinfunction "VREF_31") (pintype "bidirectional+no_connect"))
    )
    (net (code "162") (name "unconnected-(U3-VIN2-Pad4)") (class "Default")
      (node (ref "U3") (pin "4") (pinfunction "VIN2_4") (pintype "input+no_connect"))
    )
    (net (code "163") (name "unconnected-(U3-VIP2-Pad1)") (class "Default")
      (node (ref "U3") (pin "1") (pinfunction "VIP2_1") (pintype "input+no_connect"))
    )
    (net (code "164") (name "unconnected-(U4-VIN2-Pad4)") (class "Default")
      (node (ref "U4") (pin "4") (pinfunction "VIN2_4") (pintype "input+no_connect"))
    )
    (net (code "165") (name "unconnected-(U4-VIP2-Pad1)") (class "Default")
      (node (ref "U4") (pin "1") (pinfunction "VIP2_1") (pintype "input+no_connect"))
    )
    (net (code "166") (name "unconnected-(U5-NC_1-Pad3)") (class "Default")
      (node (ref "U5") (pin "3") (pinfunction "NC_1_3") (pintype "passive+no_connect"))
    )
    (net (code "167") (name "unconnected-(U5-NC_2-Pad4)") (class "Default")
      (node (ref "U5") (pin "4") (pinfunction "NC_2_4") (pintype "passive+no_connect"))
    )
    (net (code "168") (name "unconnected-(U5-NC_3-Pad13)") (class "Default")
      (node (ref "U5") (pin "13") (pinfunction "NC_3_13") (pintype "passive+no_connect"))
    )
  )
)
